# EECS430SinglePatch.net
KiCad netlist of a schematic drawn in Altium Designer
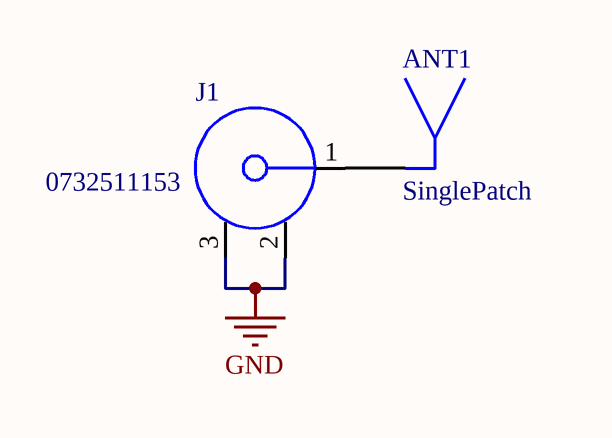
[diagram p0: EECS430SinglePatch.SchDoc]

(export (version "E")
  (design (tool "Eeschema 10.0.6"))
  (components
    (comp (ref "ANT1")
      (value "SinglePatch")
      (footprint "SinglePatch")
      (libsource (lib "EECS430PhasedArray") (part "SinglePatch"))
    )
    (comp (ref "J1")
      (value "0732511153")
      (footprint "0732511153_2Layer")
      (description "SMA Connector Jack, Female Socket 50 Ohms Board Edge, End Launch Solder")
      (libsource (lib "EECS430PhasedArray") (part "0732511153"))
    )
  )
  (nets
    (net (code "1") (name "GND") (class "Default")
      (node (ref "J1") (pin "2") (pintype "passive"))
      (node (ref "J1") (pin "3") (pintype "passive"))
    )
    (net (code "2") (name "Net-(ANT1-ANT)") (class "Default")
      (node (ref "ANT1") (pin "1") (pinfunction "ANT_1") (pintype "passive"))
      (node (ref "J1") (pin "1") (pintype "passive"))
    )
  )
)
